# motion-sensor-EasyEDA.net
KiCad netlist of a schematic drawn in EasyEDA
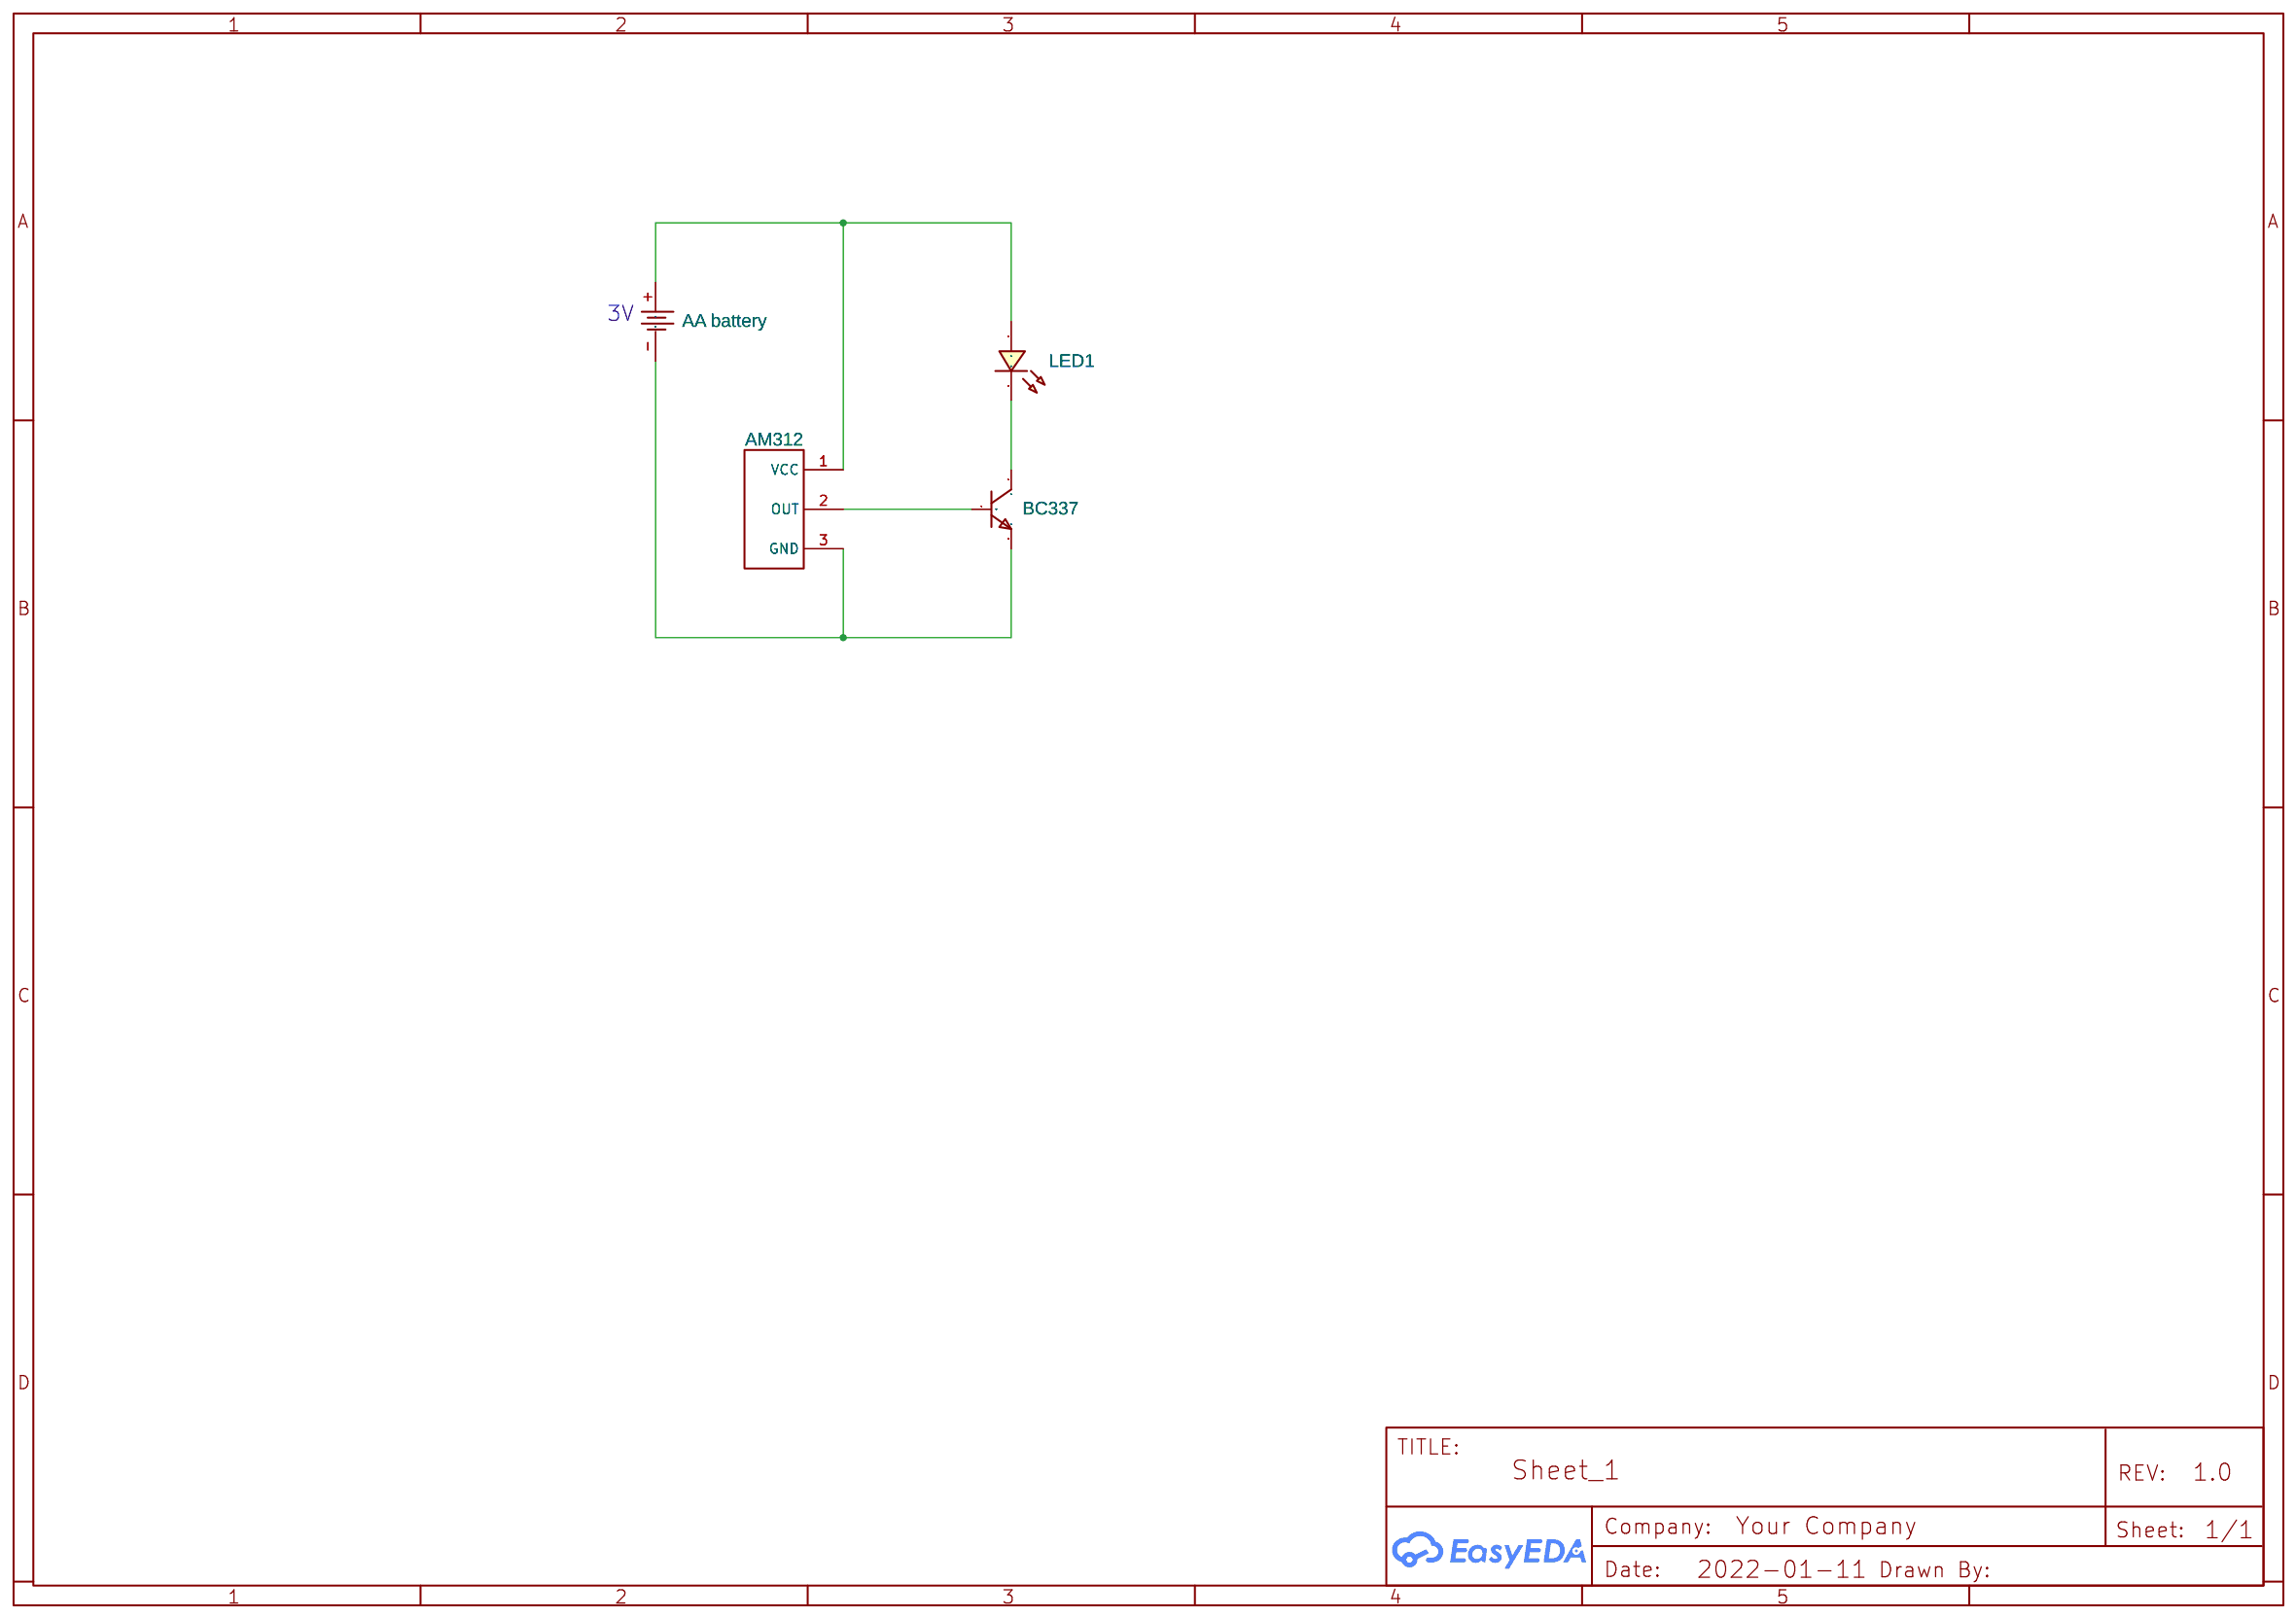
[diagram p0: schematic sheet]

(export (version "E")
  (design (tool "Eeschema 10.0.6"))
  (components
    (comp (ref "B1")
      (value "AA battery")
      (fields (field (name "BOM_Manufacturer Part") "CR1220-2") (field (name "BOM_Supplier Part") "C70381"))
      (libsource (lib "") (part "CR1220-2"))
    )
    (comp (ref "LED1")
      (value ".")
      (fields
        (field (name "BOM_Manufacturer Part") "19-217/R6C-AL1M2VY/3T")
        (field (name "BOM_Supplier Part") "C72044")
      )
      (libsource (lib "") (part "LED-0603_R"))
    )
    (comp (ref "Q1")
      (value "BC337")
      (fields (field (name "BOM_Supplier Part") "C154963"))
      (libsource (lib "") (part "BC337"))
    )
    (comp (ref "U1")
      (value "AM312")
      (fields (field (name "BOM_Supplier Part") "C114881"))
      (libsource (lib "") (part "AM312"))
    )
  )
  (nets
    (net (code "1") (name "Net-(B1-1)") (class "Default")
      (node (ref "B1") (pin "+") (pinfunction "1_+") (pintype "input"))
      (node (ref "LED1") (pin "1") (pinfunction "1_1") (pintype "unspecified"))
      (node (ref "U1") (pin "1") (pinfunction "VCC_1") (pintype "unspecified"))
    )
    (net (code "2") (name "Net-(B1-2)") (class "Default")
      (node (ref "B1") (pin "-") (pinfunction "2_-") (pintype "input"))
      (node (ref "Q1") (pin "3") (pinfunction "E_3") (pintype "unspecified"))
      (node (ref "U1") (pin "3") (pinfunction "GND_3") (pintype "unspecified"))
    )
    (net (code "3") (name "Net-(Q1-B)") (class "Default")
      (node (ref "Q1") (pin "2") (pinfunction "B_2") (pintype "unspecified"))
      (node (ref "U1") (pin "2") (pinfunction "OUT_2") (pintype "unspecified"))
    )
    (net (code "4") (name "Net-(Q1-C)") (class "Default")
      (node (ref "LED1") (pin "2") (pinfunction "2_2") (pintype "unspecified"))
      (node (ref "Q1") (pin "1") (pinfunction "C_1") (pintype "unspecified"))
    )
  )
)
